# 32sog_a.net
KiCad netlist of a schematic drawn in EAGLE
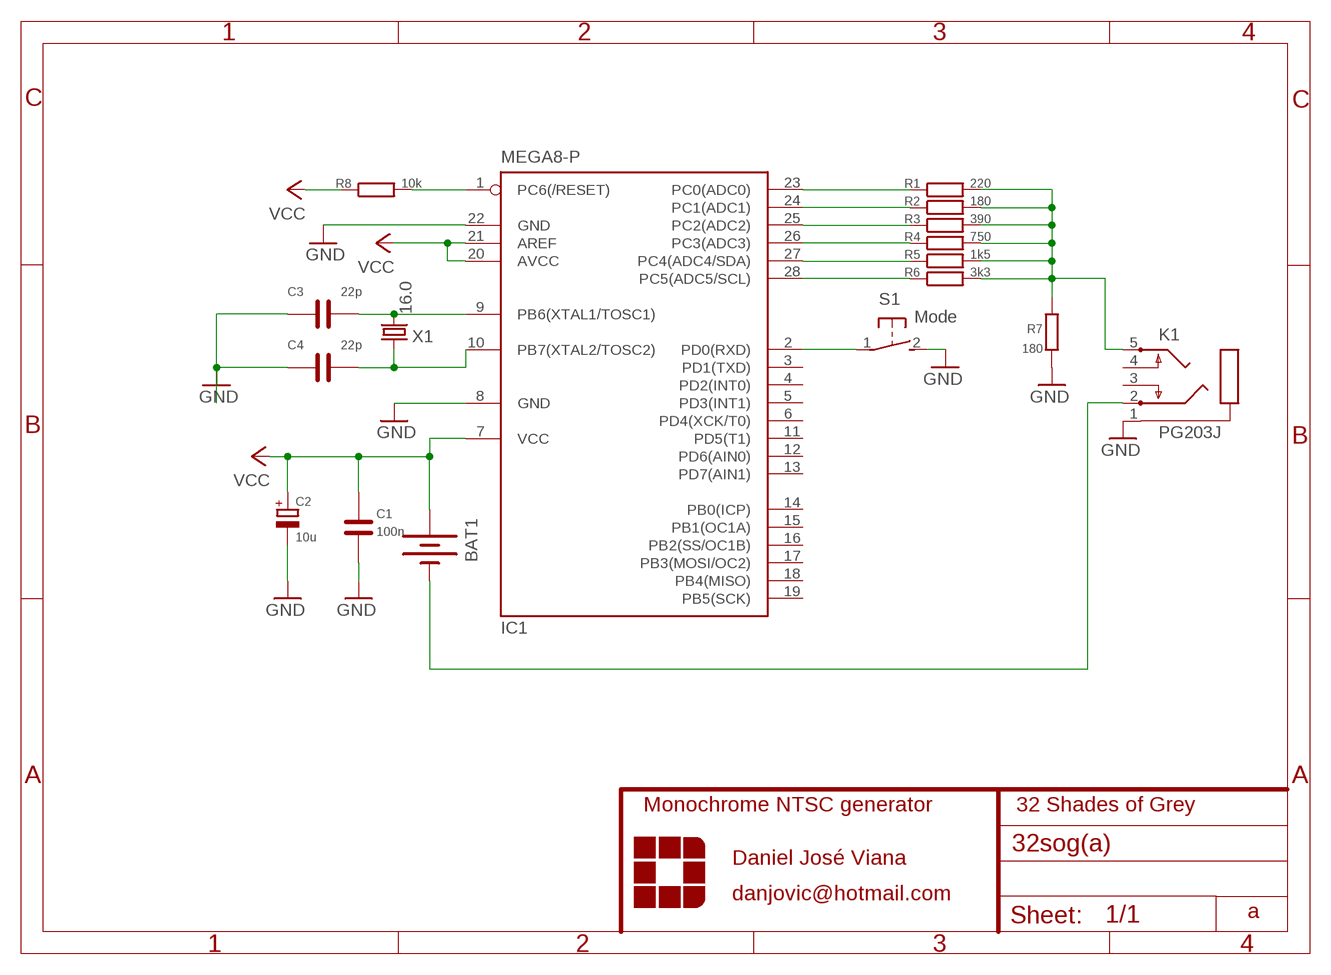
[diagram p0: schematic, sheet 1]

(export (version "E")
  (design (tool "Eeschema 10.0.6"))
  (components
    (comp (ref "BAT1")
      (value "BATTERY20PTH")
      (footprint "eagle-import:BATTCOM_20MM_PTH")
      (libsource (lib "eagle-import") (part "BATTERY20PTH"))
    )
    (comp (ref "C1")
      (value "100n")
      (footprint "eagle-import:C050-024X044")
      (libsource (lib "eagle-import") (part "CCERAMICO"))
    )
    (comp (ref "C2")
      (value "10u")
      (footprint "eagle-import:E2-4_LARGEPADS")
      (libsource (lib "eagle-import") (part "CPOL-EUE2-4_LARGEPADS"))
    )
    (comp (ref "C3")
      (value "22p")
      (footprint "eagle-import:C050-024X044")
      (libsource (lib "eagle-import") (part "CCERAMICO"))
    )
    (comp (ref "C4")
      (value "22p")
      (footprint "eagle-import:C050-024X044")
      (libsource (lib "eagle-import") (part "CCERAMICO"))
    )
    (comp (ref "IC1")
      (value "MEGA8-P")
      (footprint "eagle-import:DIL28-3")
      (libsource (lib "eagle-import") (part "MEGA8-P"))
    )
    (comp (ref "K1")
      (value "PG203J")
      (footprint "eagle-import:PG203J")
      (libsource (lib "eagle-import") (part "PG203J"))
    )
    (comp (ref "R1")
      (value "220")
      (footprint "eagle-import:0207_7")
      (libsource (lib "eagle-import") (part "R-EU_0207/7"))
    )
    (comp (ref "R2")
      (value "180")
      (footprint "eagle-import:0207_7")
      (libsource (lib "eagle-import") (part "R-EU_0207/7"))
    )
    (comp (ref "R3")
      (value "390")
      (footprint "eagle-import:0207_7")
      (libsource (lib "eagle-import") (part "R-EU_0207/7"))
    )
    (comp (ref "R4")
      (value "750")
      (footprint "eagle-import:0207_7")
      (libsource (lib "eagle-import") (part "R-EU_0207/7"))
    )
    (comp (ref "R5")
      (value "1k5")
      (footprint "eagle-import:0207_7")
      (libsource (lib "eagle-import") (part "R-EU_0207/7"))
    )
    (comp (ref "R6")
      (value "3k3")
      (footprint "eagle-import:0207_7")
      (libsource (lib "eagle-import") (part "R-EU_0207/7"))
    )
    (comp (ref "R7")
      (value "180")
      (footprint "eagle-import:0207_7")
      (libsource (lib "eagle-import") (part "R-EU_0207/7"))
    )
    (comp (ref "R8")
      (value "10k")
      (footprint "eagle-import:0207_7")
      (libsource (lib "eagle-import") (part "R-EU_0207/7"))
    )
    (comp (ref "S1")
      (value "Mode")
      (footprint "eagle-import:B3F-31XX")
      (fields (field (name "MPN") "B3F-3100"))
      (libsource (lib "eagle-import") (part "31-XX"))
    )
    (comp (ref "X1")
      (value "16.0")
      (footprint "eagle-import:HC49_S")
      (libsource (lib "eagle-import") (part "CRYSTALHC49S"))
    )
  )
  (nets
    (net (code "1") (name "GND") (class "Default")
      (node (ref "C1") (pin "1") (pinfunction "P$1_1") (pintype "bidirectional"))
      (node (ref "C2") (pin "-") (pinfunction "-_-") (pintype "passive"))
      (node (ref "C3") (pin "1") (pinfunction "P$1_1") (pintype "bidirectional"))
      (node (ref "C4") (pin "1") (pinfunction "P$1_1") (pintype "bidirectional"))
      (node (ref "IC1") (pin "22") (pinfunction "GND_22") (pintype "power_in"))
      (node (ref "IC1") (pin "8") (pinfunction "GND_8") (pintype "power_in"))
      (node (ref "K1") (pin "1") (pinfunction "1_1") (pintype "passive"))
      (node (ref "R7") (pin "2") (pinfunction "2_2") (pintype "passive"))
      (node (ref "S1") (pin "2") (pinfunction "S_2") (pintype "passive"))
    )
    (net (code "2") (name "Net-(BAT1--)") (class "Default")
      (node (ref "BAT1") (pin "2") (pinfunction "-_2") (pintype "power_in"))
      (node (ref "K1") (pin "2") (pinfunction "2_2") (pintype "passive"))
    )
    (net (code "3") (name "Net-(C3-P$2)") (class "Default")
      (node (ref "C3") (pin "2") (pinfunction "P$2_2") (pintype "bidirectional"))
      (node (ref "IC1") (pin "9") (pinfunction "PB6(XTAL1/TOSC1)_9") (pintype "bidirectional"))
      (node (ref "X1") (pin "2") (pinfunction "2_2") (pintype "passive"))
    )
    (net (code "4") (name "Net-(C4-P$2)") (class "Default")
      (node (ref "C4") (pin "2") (pinfunction "P$2_2") (pintype "bidirectional"))
      (node (ref "IC1") (pin "10") (pinfunction "PB7(XTAL2/TOSC2)_10") (pintype "bidirectional"))
      (node (ref "X1") (pin "1") (pinfunction "1_1") (pintype "passive"))
    )
    (net (code "5") (name "Net-(IC1-PC0(ADC0))") (class "Default")
      (node (ref "IC1") (pin "23") (pinfunction "PC0(ADC0)_23") (pintype "bidirectional"))
      (node (ref "R1") (pin "1") (pinfunction "1_1") (pintype "passive"))
    )
    (net (code "6") (name "Net-(IC1-PC1(ADC1))") (class "Default")
      (node (ref "IC1") (pin "24") (pinfunction "PC1(ADC1)_24") (pintype "bidirectional"))
      (node (ref "R2") (pin "1") (pinfunction "1_1") (pintype "passive"))
    )
    (net (code "7") (name "Net-(IC1-PC2(ADC2))") (class "Default")
      (node (ref "IC1") (pin "25") (pinfunction "PC2(ADC2)_25") (pintype "bidirectional"))
      (node (ref "R3") (pin "1") (pinfunction "1_1") (pintype "passive"))
    )
    (net (code "8") (name "Net-(IC1-PC3(ADC3))") (class "Default")
      (node (ref "IC1") (pin "26") (pinfunction "PC3(ADC3)_26") (pintype "bidirectional"))
      (node (ref "R4") (pin "1") (pinfunction "1_1") (pintype "passive"))
    )
    (net (code "9") (name "Net-(IC1-PC4(ADC4{slash}SDA))") (class "Default")
      (node (ref "IC1") (pin "27") (pinfunction "PC4(ADC4/SDA)_27") (pintype "bidirectional"))
      (node (ref "R5") (pin "1") (pinfunction "1_1") (pintype "passive"))
    )
    (net (code "10") (name "Net-(IC1-PC5(ADC5{slash}SCL))") (class "Default")
      (node (ref "IC1") (pin "28") (pinfunction "PC5(ADC5/SCL)_28") (pintype "bidirectional"))
      (node (ref "R6") (pin "1") (pinfunction "1_1") (pintype "passive"))
    )
    (net (code "11") (name "Net-(IC1-PC6({slash}RESET))") (class "Default")
      (node (ref "IC1") (pin "1") (pinfunction "PC6(/RESET)_1") (pintype "bidirectional"))
      (node (ref "R8") (pin "2") (pinfunction "2_2") (pintype "passive"))
    )
    (net (code "12") (name "Net-(IC1-PD0(RXD))") (class "Default")
      (node (ref "IC1") (pin "2") (pinfunction "PD0(RXD)_2") (pintype "bidirectional"))
      (node (ref "S1") (pin "1") (pinfunction "P_1") (pintype "passive"))
    )
    (net (code "13") (name "Net-(K1-Pad5)") (class "Default")
      (node (ref "K1") (pin "5") (pinfunction "5_5") (pintype "passive"))
      (node (ref "R1") (pin "2") (pinfunction "2_2") (pintype "passive"))
      (node (ref "R2") (pin "2") (pinfunction "2_2") (pintype "passive"))
      (node (ref "R3") (pin "2") (pinfunction "2_2") (pintype "passive"))
      (node (ref "R4") (pin "2") (pinfunction "2_2") (pintype "passive"))
      (node (ref "R5") (pin "2") (pinfunction "2_2") (pintype "passive"))
      (node (ref "R6") (pin "2") (pinfunction "2_2") (pintype "passive"))
      (node (ref "R7") (pin "1") (pinfunction "1_1") (pintype "passive"))
    )
    (net (code "14") (name "VCC") (class "Default")
      (node (ref "BAT1") (pin "1") (pinfunction "+_1") (pintype "power_in"))
      (node (ref "C1") (pin "2") (pinfunction "P$2_2") (pintype "bidirectional"))
      (node (ref "C2") (pin "+") (pinfunction "+_+") (pintype "passive"))
      (node (ref "IC1") (pin "20") (pinfunction "AVCC_20") (pintype "power_in"))
      (node (ref "IC1") (pin "21") (pinfunction "AREF_21") (pintype "passive"))
      (node (ref "IC1") (pin "7") (pinfunction "VCC_7") (pintype "power_in"))
      (node (ref "R8") (pin "1") (pinfunction "1_1") (pintype "passive"))
    )
    (net (code "15") (name "unconnected-(IC1-PB0(ICP)-Pad14)") (class "Default")
      (node (ref "IC1") (pin "14") (pinfunction "PB0(ICP)_14") (pintype "bidirectional"))
    )
    (net (code "16") (name "unconnected-(IC1-PB1(OC1A)-Pad15)") (class "Default")
      (node (ref "IC1") (pin "15") (pinfunction "PB1(OC1A)_15") (pintype "bidirectional"))
    )
    (net (code "17") (name "unconnected-(IC1-PB2(SS{slash}OC1B)-Pad16)") (class "Default")
      (node (ref "IC1") (pin "16") (pinfunction "PB2(SS/OC1B)_16") (pintype "bidirectional"))
    )
    (net (code "18") (name "unconnected-(IC1-PB3(MOSI{slash}OC2)-Pad17)") (class "Default")
      (node (ref "IC1") (pin "17") (pinfunction "PB3(MOSI/OC2)_17") (pintype "bidirectional"))
    )
    (net (code "19") (name "unconnected-(IC1-PB4(MISO)-Pad18)") (class "Default")
      (node (ref "IC1") (pin "18") (pinfunction "PB4(MISO)_18") (pintype "bidirectional"))
    )
    (net (code "20") (name "unconnected-(IC1-PB5(SCK)-Pad19)") (class "Default")
      (node (ref "IC1") (pin "19") (pinfunction "PB5(SCK)_19") (pintype "bidirectional"))
    )
    (net (code "21") (name "unconnected-(IC1-PD1(TXD)-Pad3)") (class "Default")
      (node (ref "IC1") (pin "3") (pinfunction "PD1(TXD)_3") (pintype "bidirectional"))
    )
    (net (code "22") (name "unconnected-(IC1-PD2(INT0)-Pad4)") (class "Default")
      (node (ref "IC1") (pin "4") (pinfunction "PD2(INT0)_4") (pintype "bidirectional"))
    )
    (net (code "23") (name "unconnected-(IC1-PD3(INT1)-Pad5)") (class "Default")
      (node (ref "IC1") (pin "5") (pinfunction "PD3(INT1)_5") (pintype "bidirectional"))
    )
    (net (code "24") (name "unconnected-(IC1-PD4(XCK{slash}T0)-Pad6)") (class "Default")
      (node (ref "IC1") (pin "6") (pinfunction "PD4(XCK/T0)_6") (pintype "bidirectional"))
    )
    (net (code "25") (name "unconnected-(IC1-PD5(T1)-Pad11)") (class "Default")
      (node (ref "IC1") (pin "11") (pinfunction "PD5(T1)_11") (pintype "bidirectional"))
    )
    (net (code "26") (name "unconnected-(IC1-PD6(AIN0)-Pad12)") (class "Default")
      (node (ref "IC1") (pin "12") (pinfunction "PD6(AIN0)_12") (pintype "bidirectional"))
    )
    (net (code "27") (name "unconnected-(IC1-PD7(AIN1)-Pad13)") (class "Default")
      (node (ref "IC1") (pin "13") (pinfunction "PD7(AIN1)_13") (pintype "bidirectional"))
    )
    (net (code "28") (name "unconnected-(K1-Pad3)") (class "Default")
      (node (ref "K1") (pin "3") (pinfunction "3_3") (pintype "passive"))
    )
    (net (code "29") (name "unconnected-(K1-Pad4)") (class "Default")
      (node (ref "K1") (pin "4") (pinfunction "4_4") (pintype "passive"))
    )
  )
)
